# source_eagle.net
KiCad netlist of a schematic drawn in EAGLE
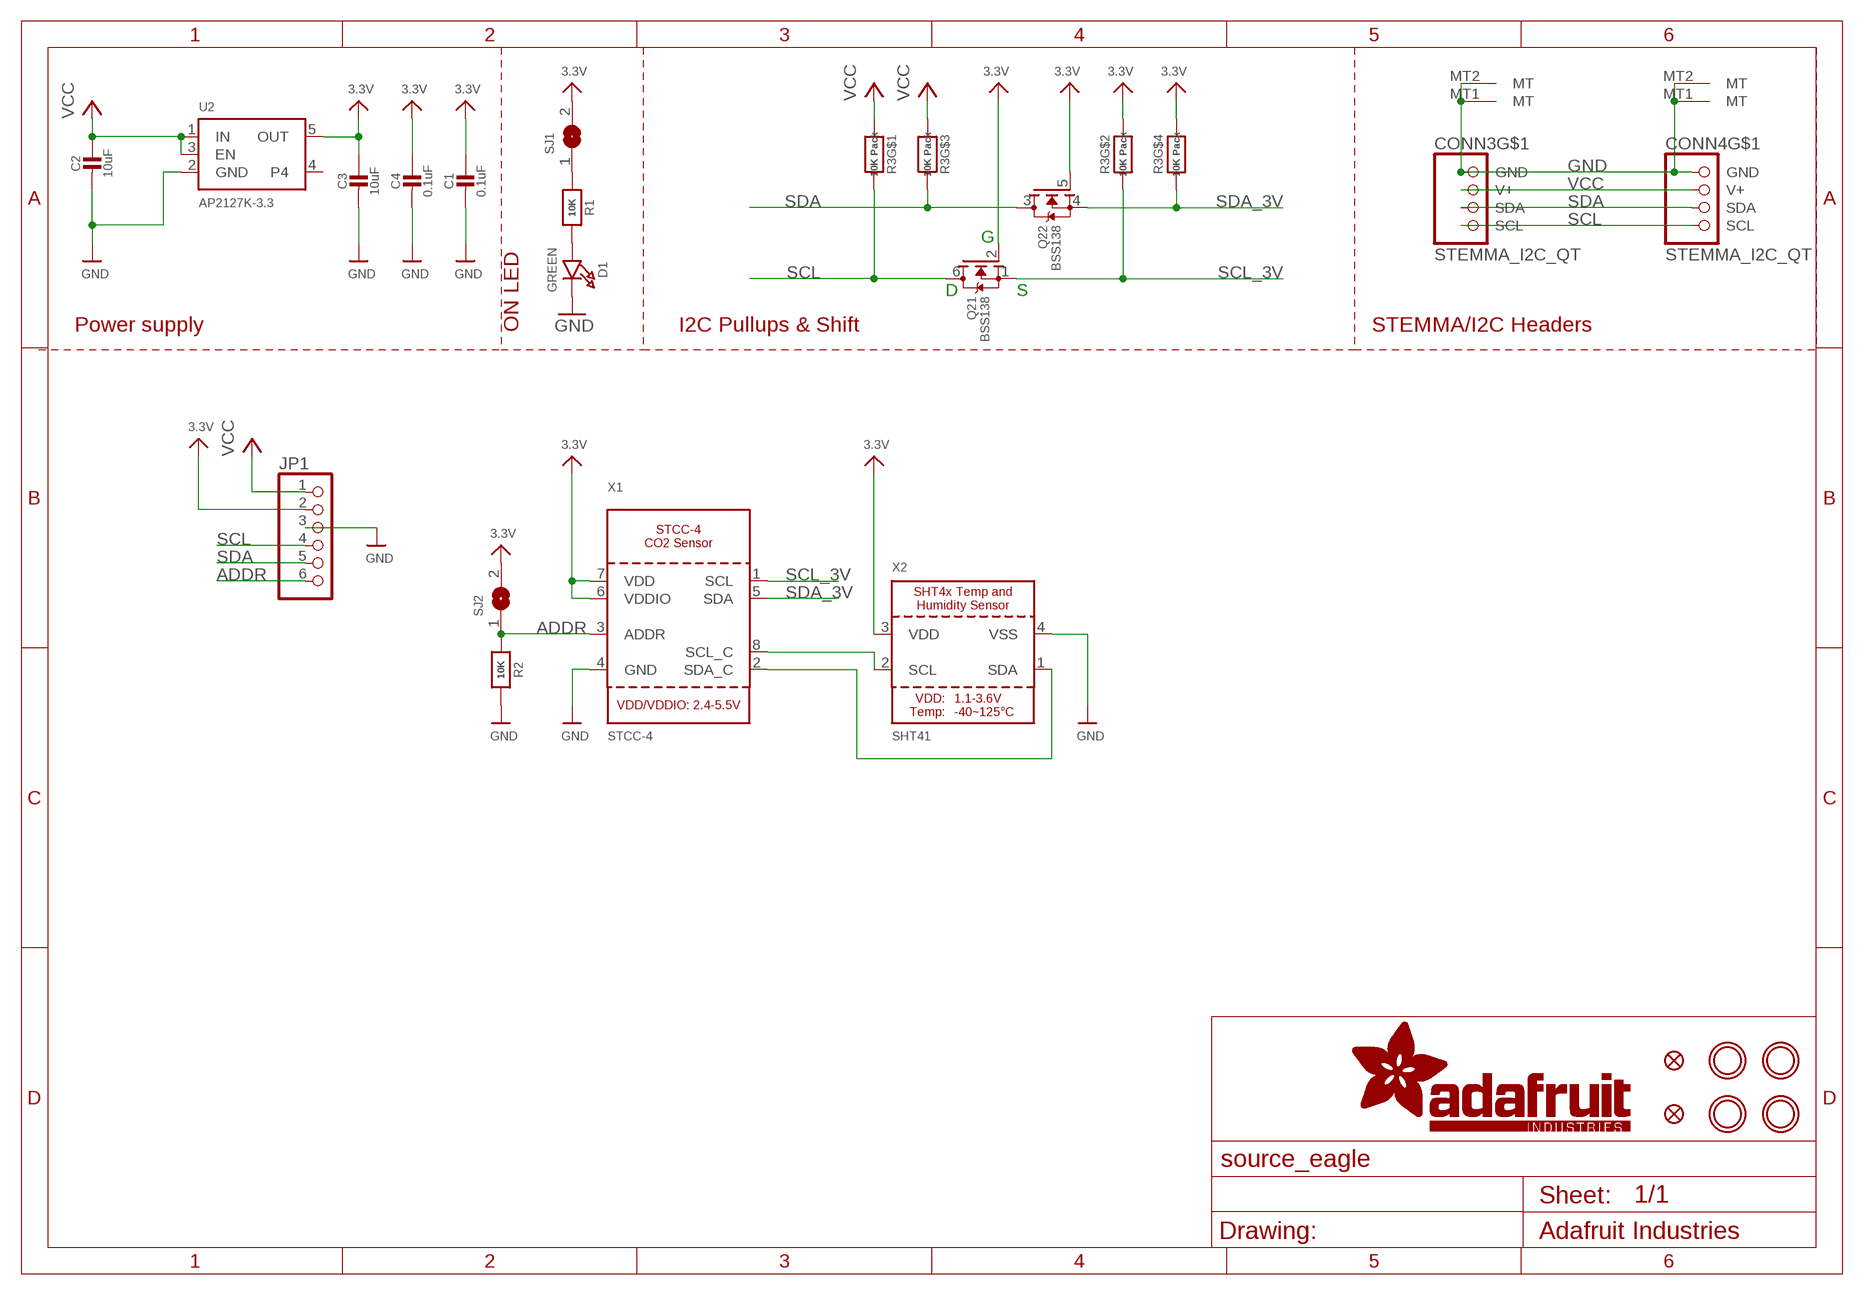
[diagram p0: schematic, sheet 1]

(export (version "E")
  (design (tool "Eeschema 10.0.6"))
  (components
    (comp (ref "C1")
      (value "0.1uF")
      (footprint "eagle-import:0603-NO")
      (libsource (lib "eagle-import") (part "CAP_CERAMIC0603_NO"))
    )
    (comp (ref "C2")
      (value "10uF")
      (footprint "eagle-import:0805-NO")
      (libsource (lib "eagle-import") (part "CAP_CERAMIC0805-NOOUTLINE"))
    )
    (comp (ref "C3")
      (value "10uF")
      (footprint "eagle-import:0805-NO")
      (libsource (lib "eagle-import") (part "CAP_CERAMIC0805-NOOUTLINE"))
    )
    (comp (ref "C4")
      (value "0.1uF")
      (footprint "eagle-import:0603-NO")
      (libsource (lib "eagle-import") (part "CAP_CERAMIC0603_NO"))
    )
    (comp (ref "CONN3")
      (value "STEMMA_I2C_QT")
      (footprint "eagle-import:JST_SH4")
      (libsource (lib "eagle-import") (part "STEMMA_I2C_QT"))
    )
    (comp (ref "CONN4")
      (value "STEMMA_I2C_QT")
      (footprint "eagle-import:JST_SH4")
      (libsource (lib "eagle-import") (part "STEMMA_I2C_QT"))
    )
    (comp (ref "D1")
      (value "GREEN")
      (footprint "eagle-import:CHIPLED_0603_NOOUTLINE")
      (libsource (lib "eagle-import") (part "LED0603_NOOUTLINE"))
    )
    (comp (ref "FID3")
      (value "FIDUCIAL_0.5MM")
      (footprint "eagle-import:FIDUCIAL_0.5MM")
      (libsource (lib "eagle-import") (part "FIDUCIAL_0.5MM"))
    )
    (comp (ref "FID4")
      (value "FIDUCIAL_0.5MM")
      (footprint "eagle-import:FIDUCIAL_0.5MM")
      (libsource (lib "eagle-import") (part "FIDUCIAL_0.5MM"))
    )
    (comp (ref "JP1")
      (value "HEADER-1X670MIL")
      (footprint "eagle-import:1X06_ROUND_70")
      (libsource (lib "eagle-import") (part "HEADER-1X670MIL"))
    )
    (comp (ref "Q2")
      (value "BSS138")
      (footprint "eagle-import:SOT363")
      (libsource (lib "eagle-import") (part "MOSFET-N_DUAL"))
    )
    (comp (ref "R1")
      (value "10K")
      (footprint "eagle-import:0603-NO")
      (libsource (lib "eagle-import") (part "RESISTOR_0603_NOOUT"))
    )
    (comp (ref "R2")
      (value "10K")
      (footprint "eagle-import:0603-NO")
      (libsource (lib "eagle-import") (part "RESISTOR_0603_NOOUT"))
    )
    (comp (ref "R3")
      (value "10K Pack")
      (footprint "eagle-import:RESPACK_4X0603")
      (libsource (lib "eagle-import") (part "RESISTOR_4PACK"))
    )
    (comp (ref "SJ1")
      (value "SOLDERJUMPERCLOSED")
      (footprint "eagle-import:SOLDERJUMPER_CLOSEDWIRE")
      (libsource (lib "eagle-import") (part "SOLDERJUMPERCLOSED"))
    )
    (comp (ref "SJ2")
      (value "SOLDERJUMPER")
      (footprint "eagle-import:SOLDERJUMPER_ARROW_NOPASTE")
      (libsource (lib "eagle-import") (part "SOLDERJUMPER"))
    )
    (comp (ref "U$1")
      (value "MOUNTINGHOLE2.5")
      (footprint "eagle-import:MOUNTINGHOLE_2.5_PLATED")
      (libsource (lib "eagle-import") (part "MOUNTINGHOLE2.5"))
    )
    (comp (ref "U$17")
      (value "MOUNTINGHOLE2.5")
      (footprint "eagle-import:MOUNTINGHOLE_2.5_PLATED")
      (libsource (lib "eagle-import") (part "MOUNTINGHOLE2.5"))
    )
    (comp (ref "U$19")
      (value "MOUNTINGHOLE2.5")
      (footprint "eagle-import:MOUNTINGHOLE_2.5_PLATED")
      (libsource (lib "eagle-import") (part "MOUNTINGHOLE2.5"))
    )
    (comp (ref "U$21")
      (value "MOUNTINGHOLE2.5")
      (footprint "eagle-import:MOUNTINGHOLE_2.5_PLATED")
      (libsource (lib "eagle-import") (part "MOUNTINGHOLE2.5"))
    )
    (comp (ref "U2")
      (value "AP2127K-3.3")
      (footprint "eagle-import:SOT23-5")
      (libsource (lib "eagle-import") (part "VREG_SOT23-5"))
    )
    (comp (ref "X1")
      (value "STCC-4")
      (footprint "eagle-import:STCC4")
      (libsource (lib "eagle-import") (part "STCC-4"))
    )
    (comp (ref "X2")
      (value "SHT41")
      (footprint "eagle-import:SHT4X")
      (libsource (lib "eagle-import") (part "SHT4X_"))
    )
  )
  (nets
    (net (code "1") (name "/ADDR") (class "Default")
      (node (ref "JP1") (pin "6") (pinfunction "6_6") (pintype "passive"))
      (node (ref "R2") (pin "1") (pinfunction "1_1") (pintype "passive"))
      (node (ref "SJ2") (pin "1") (pinfunction "1_1") (pintype "passive"))
      (node (ref "X1") (pin "3") (pinfunction "ADDR_3") (pintype "input"))
    )
    (net (code "2") (name "/SCL") (class "Default")
      (node (ref "CONN3") (pin "4") (pinfunction "SCL_4") (pintype "passive"))
      (node (ref "CONN4") (pin "4") (pinfunction "SCL_4") (pintype "passive"))
      (node (ref "JP1") (pin "4") (pinfunction "4_4") (pintype "passive"))
      (node (ref "Q2") (pin "6") (pinfunction "D_6") (pintype "bidirectional"))
      (node (ref "R3") (pin "8") (pinfunction "2_8") (pintype "passive"))
    )
    (net (code "3") (name "/SCL_3V") (class "Default")
      (node (ref "Q2") (pin "1") (pinfunction "S_1") (pintype "bidirectional"))
      (node (ref "R3") (pin "7") (pinfunction "2_7") (pintype "passive"))
      (node (ref "X1") (pin "1") (pinfunction "SCL_1") (pintype "input"))
    )
    (net (code "4") (name "/SDA") (class "Default")
      (node (ref "CONN3") (pin "3") (pinfunction "SDA_3") (pintype "passive"))
      (node (ref "CONN4") (pin "3") (pinfunction "SDA_3") (pintype "passive"))
      (node (ref "JP1") (pin "5") (pinfunction "5_5") (pintype "passive"))
      (node (ref "Q2") (pin "3") (pinfunction "D_3") (pintype "bidirectional"))
      (node (ref "R3") (pin "6") (pinfunction "2_6") (pintype "passive"))
    )
    (net (code "5") (name "/SDA_3V") (class "Default")
      (node (ref "Q2") (pin "4") (pinfunction "S_4") (pintype "bidirectional"))
      (node (ref "R3") (pin "5") (pinfunction "2_5") (pintype "passive"))
      (node (ref "X1") (pin "5") (pinfunction "SDA_5") (pintype "bidirectional"))
    )
    (net (code "6") (name "3.3V") (class "Default")
      (node (ref "C1") (pin "1") (pinfunction "1_1") (pintype "passive"))
      (node (ref "C3") (pin "1") (pinfunction "1_1") (pintype "passive"))
      (node (ref "C4") (pin "1") (pinfunction "1_1") (pintype "passive"))
      (node (ref "JP1") (pin "2") (pinfunction "2_2") (pintype "passive"))
      (node (ref "Q2") (pin "2") (pinfunction "G_2") (pintype "bidirectional"))
      (node (ref "Q2") (pin "5") (pinfunction "G_5") (pintype "bidirectional"))
      (node (ref "R3") (pin "2") (pinfunction "1_2") (pintype "passive"))
      (node (ref "R3") (pin "4") (pinfunction "1_4") (pintype "passive"))
      (node (ref "SJ1") (pin "2") (pinfunction "2_2") (pintype "passive"))
      (node (ref "SJ2") (pin "2") (pinfunction "2_2") (pintype "passive"))
      (node (ref "U2") (pin "5") (pinfunction "OUT_5") (pintype "power_in"))
      (node (ref "X1") (pin "6") (pinfunction "VDDIO_6") (pintype "power_in"))
      (node (ref "X1") (pin "7") (pinfunction "VDD_7") (pintype "power_in"))
      (node (ref "X2") (pin "3") (pinfunction "VDD_3") (pintype "power_in"))
    )
    (net (code "7") (name "GND") (class "Default")
      (node (ref "C1") (pin "2") (pinfunction "2_2") (pintype "passive"))
      (node (ref "C2") (pin "2") (pinfunction "2_2") (pintype "passive"))
      (node (ref "C3") (pin "2") (pinfunction "2_2") (pintype "passive"))
      (node (ref "C4") (pin "2") (pinfunction "2_2") (pintype "passive"))
      (node (ref "CONN3") (pin "1") (pinfunction "GND_1") (pintype "passive"))
      (node (ref "CONN3") (pin "MT1") (pinfunction "MT_MT1") (pintype "bidirectional"))
      (node (ref "CONN3") (pin "MT2") (pinfunction "MT_MT2") (pintype "bidirectional"))
      (node (ref "CONN4") (pin "1") (pinfunction "GND_1") (pintype "passive"))
      (node (ref "CONN4") (pin "MT1") (pinfunction "MT_MT1") (pintype "bidirectional"))
      (node (ref "CONN4") (pin "MT2") (pinfunction "MT_MT2") (pintype "bidirectional"))
      (node (ref "D1") (pin "C") (pinfunction "C_C") (pintype "passive"))
      (node (ref "JP1") (pin "3") (pinfunction "3_3") (pintype "passive"))
      (node (ref "R2") (pin "2") (pinfunction "2_2") (pintype "passive"))
      (node (ref "U2") (pin "2") (pinfunction "GND_2") (pintype "power_in"))
      (node (ref "X1") (pin "4") (pinfunction "GND_4") (pintype "power_in"))
      (node (ref "X2") (pin "4") (pinfunction "VSS_4") (pintype "power_in"))
    )
    (net (code "8") (name "Net-(D1-PadA)") (class "Default")
      (node (ref "D1") (pin "A") (pinfunction "A_A") (pintype "passive"))
      (node (ref "R1") (pin "2") (pinfunction "2_2") (pintype "passive"))
    )
    (net (code "9") (name "Net-(R1-Pad1)") (class "Default")
      (node (ref "R1") (pin "1") (pinfunction "1_1") (pintype "passive"))
      (node (ref "SJ1") (pin "1") (pinfunction "1_1") (pintype "passive"))
    )
    (net (code "10") (name "Net-(X1-SCL_C)") (class "Default")
      (node (ref "X1") (pin "8") (pinfunction "SCL_C_8") (pintype "output"))
      (node (ref "X2") (pin "2") (pinfunction "SCL_2") (pintype "bidirectional"))
    )
    (net (code "11") (name "Net-(X1-SDA_C)") (class "Default")
      (node (ref "X1") (pin "2") (pinfunction "SDA_C_2") (pintype "bidirectional"))
      (node (ref "X2") (pin "1") (pinfunction "SDA_1") (pintype "bidirectional"))
    )
    (net (code "12") (name "VCC") (class "Default")
      (node (ref "C2") (pin "1") (pinfunction "1_1") (pintype "passive"))
      (node (ref "CONN3") (pin "2") (pinfunction "V+_2") (pintype "passive"))
      (node (ref "CONN4") (pin "2") (pinfunction "V+_2") (pintype "passive"))
      (node (ref "JP1") (pin "1") (pinfunction "1_1") (pintype "passive"))
      (node (ref "R3") (pin "1") (pinfunction "1_1") (pintype "passive"))
      (node (ref "R3") (pin "3") (pinfunction "1_3") (pintype "passive"))
      (node (ref "U2") (pin "1") (pinfunction "IN_1") (pintype "power_in"))
      (node (ref "U2") (pin "3") (pinfunction "EN_3") (pintype "input"))
    )
    (net (code "13") (name "unconnected-(U2-P4-Pad4)") (class "Default")
      (node (ref "U2") (pin "4") (pinfunction "P4_4") (pintype "bidirectional"))
    )
  )
)
